# SCH_Lood_2024-08-15.net
KiCad netlist of a schematic drawn in EasyEDA
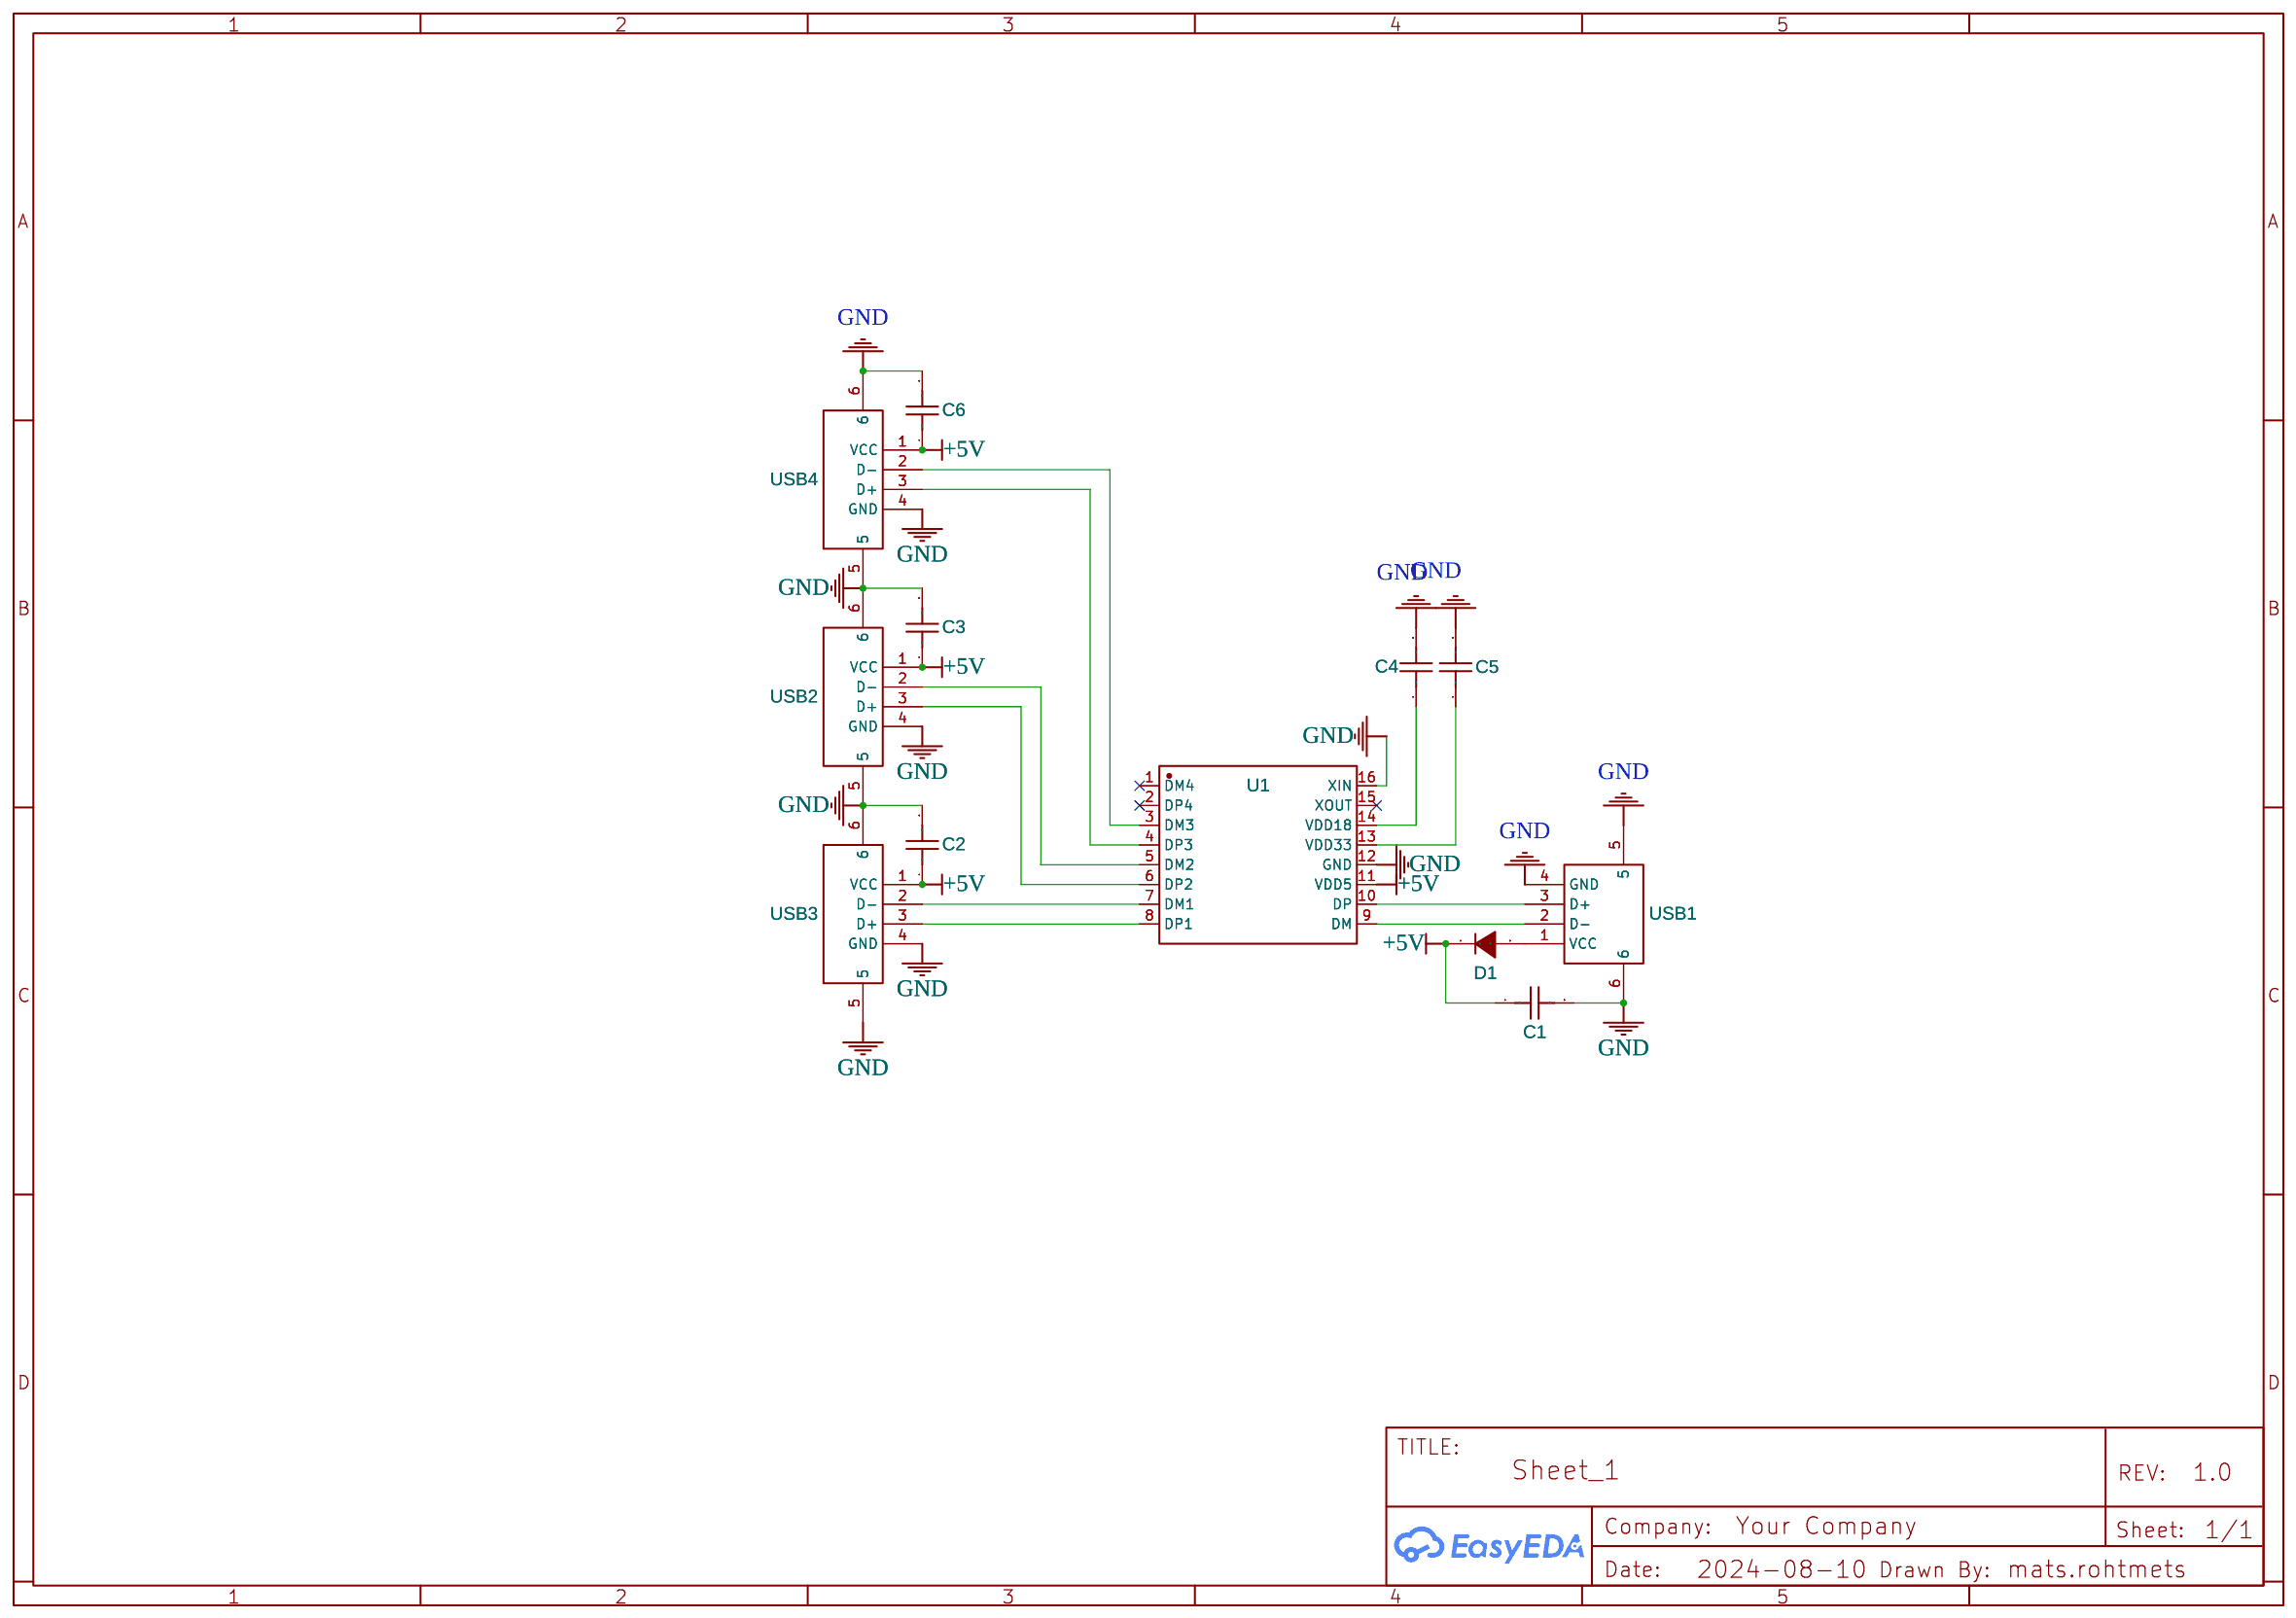
[diagram p0: schematic sheet]

(export (version "E")
  (design (tool "Eeschema 10.0.6"))
  (components
    (comp (ref "C1")
      (value "10uF")
      (fields
        (field (name "Manufacturer Part") "CL10A106KP8NNNC")
        (field (name "Manufacturer") "SAMSUNG(三星)")
      )
      (libsource (lib "") (part "CL10A106KP8NNNC_1"))
    )
    (comp (ref "C2")
      (value "10uF")
      (fields
        (field (name "Manufacturer Part") "CL10A106KP8NNNC")
        (field (name "Manufacturer") "SAMSUNG(三星)")
      )
      (libsource (lib "") (part "CL10A106KP8NNNC"))
    )
    (comp (ref "C3")
      (value "10uF")
      (fields
        (field (name "Manufacturer Part") "CL10A106KP8NNNC")
        (field (name "Manufacturer") "SAMSUNG(三星)")
      )
      (libsource (lib "") (part "CL10A106KP8NNNC"))
    )
    (comp (ref "C4")
      (value "10uF")
      (fields
        (field (name "Manufacturer Part") "CL10A106KP8NNNC")
        (field (name "Manufacturer") "SAMSUNG(三星)")
      )
      (libsource (lib "") (part "CL10A106KP8NNNC"))
    )
    (comp (ref "C5")
      (value "10uF")
      (fields
        (field (name "Manufacturer Part") "CL10A106KP8NNNC")
        (field (name "Manufacturer") "SAMSUNG(三星)")
      )
      (libsource (lib "") (part "CL10A106KP8NNNC"))
    )
    (comp (ref "C6")
      (value "10uF")
      (fields
        (field (name "Manufacturer Part") "CL10A106KP8NNNC")
        (field (name "Manufacturer") "SAMSUNG(三星)")
      )
      (libsource (lib "") (part "CL10A106KP8NNNC"))
    )
    (comp (ref "D1")
      (value "NSR0320MW2T1G")
      (fields (field (name "Manufacturer") "onsemi(安森美)"))
      (libsource (lib "") (part "NSR0320MW2T1G"))
    )
    (comp (ref "U1")
      (value "SL2.1A")
      (fields (field (name "Manufacturer") "CoreChips(和芯润德)"))
      (libsource (lib "") (part "SL2.1A"))
    )
    (comp (ref "USB1")
      (value "U-G-04DD-W-01")
      (fields (field (name "Manufacturer Part") "U-G-O4DD-W-1") (field (name "Manufacturer") "韩国韩荣"))
      (libsource (lib "") (part "U-G-04DD-W-01"))
    )
    (comp (ref "USB2")
      (value "USB-AF-90-14.4X13.6-H7.0-DIP")
      (fields (field (name "Manufacturer Part") "903-131A1011D10100") (field (name "Manufacturer") "精拓金"))
      (libsource (lib "") (part "USB-AF-90-14.4X13.6-H7.0-DIP"))
    )
    (comp (ref "USB3")
      (value "USB-AF-90-14.4X13.6-H7.0-DIP")
      (fields (field (name "Manufacturer Part") "903-131A1011D10100") (field (name "Manufacturer") "精拓金"))
      (libsource (lib "") (part "USB-AF-90-14.4X13.6-H7.0-DIP"))
    )
    (comp (ref "USB4")
      (value "USB-AF-90-14.4X13.6-H7.0-DIP")
      (fields (field (name "Manufacturer Part") "903-131A1011D10100") (field (name "Manufacturer") "精拓金"))
      (libsource (lib "") (part "USB-AF-90-14.4X13.6-H7.0-DIP"))
    )
  )
  (nets
    (net (code "1") (name "+5V") (class "Default")
      (node (ref "C1") (pin "1") (pinfunction "1_1") (pintype "unspecified"))
      (node (ref "C2") (pin "1") (pinfunction "1_1") (pintype "unspecified"))
      (node (ref "C3") (pin "1") (pinfunction "1_1") (pintype "unspecified"))
      (node (ref "C6") (pin "1") (pinfunction "1_1") (pintype "unspecified"))
      (node (ref "D1") (pin "1") (pinfunction "C_1") (pintype "unspecified"))
      (node (ref "U1") (pin "11") (pinfunction "VDD5_11") (pintype "unspecified"))
      (node (ref "USB2") (pin "1") (pinfunction "VCC_1") (pintype "unspecified"))
      (node (ref "USB3") (pin "1") (pinfunction "VCC_1") (pintype "unspecified"))
      (node (ref "USB4") (pin "1") (pinfunction "VCC_1") (pintype "unspecified"))
    )
    (net (code "2") (name "GND") (class "Default")
      (node (ref "C1") (pin "2") (pinfunction "2_2") (pintype "unspecified"))
      (node (ref "C2") (pin "2") (pinfunction "2_2") (pintype "unspecified"))
      (node (ref "C3") (pin "2") (pinfunction "2_2") (pintype "unspecified"))
      (node (ref "C4") (pin "2") (pinfunction "2_2") (pintype "unspecified"))
      (node (ref "C5") (pin "2") (pinfunction "2_2") (pintype "unspecified"))
      (node (ref "C6") (pin "2") (pinfunction "2_2") (pintype "unspecified"))
      (node (ref "U1") (pin "12") (pinfunction "GND_12") (pintype "unspecified"))
      (node (ref "U1") (pin "16") (pinfunction "XIN_16") (pintype "unspecified"))
      (node (ref "USB1") (pin "4") (pinfunction "GND_4") (pintype "unspecified"))
      (node (ref "USB1") (pin "5") (pinfunction "5_5") (pintype "unspecified"))
      (node (ref "USB1") (pin "6") (pinfunction "6_6") (pintype "unspecified"))
      (node (ref "USB2") (pin "4") (pinfunction "GND_4") (pintype "unspecified"))
      (node (ref "USB2") (pin "5") (pinfunction "5_5") (pintype "unspecified"))
      (node (ref "USB2") (pin "6") (pinfunction "6_6") (pintype "unspecified"))
      (node (ref "USB3") (pin "4") (pinfunction "GND_4") (pintype "unspecified"))
      (node (ref "USB3") (pin "5") (pinfunction "5_5") (pintype "unspecified"))
      (node (ref "USB3") (pin "6") (pinfunction "6_6") (pintype "unspecified"))
      (node (ref "USB4") (pin "4") (pinfunction "GND_4") (pintype "unspecified"))
      (node (ref "USB4") (pin "5") (pinfunction "5_5") (pintype "unspecified"))
      (node (ref "USB4") (pin "6") (pinfunction "6_6") (pintype "unspecified"))
    )
    (net (code "3") (name "Net-(D1-A)") (class "Default")
      (node (ref "D1") (pin "2") (pinfunction "A_2") (pintype "unspecified"))
      (node (ref "USB1") (pin "1") (pinfunction "VCC_1") (pintype "unspecified"))
    )
    (net (code "4") (name "Net-(U1-DM)") (class "Default")
      (node (ref "U1") (pin "9") (pinfunction "DM_9") (pintype "unspecified"))
      (node (ref "USB1") (pin "2") (pinfunction "D-_2") (pintype "unspecified"))
    )
    (net (code "5") (name "Net-(U1-DM1)") (class "Default")
      (node (ref "U1") (pin "7") (pinfunction "DM1_7") (pintype "unspecified"))
      (node (ref "USB3") (pin "2") (pinfunction "D-_2") (pintype "unspecified"))
    )
    (net (code "6") (name "Net-(U1-DM2)") (class "Default")
      (node (ref "U1") (pin "5") (pinfunction "DM2_5") (pintype "unspecified"))
      (node (ref "USB2") (pin "2") (pinfunction "D-_2") (pintype "unspecified"))
    )
    (net (code "7") (name "Net-(U1-DM3)") (class "Default")
      (node (ref "U1") (pin "3") (pinfunction "DM3_3") (pintype "unspecified"))
      (node (ref "USB4") (pin "2") (pinfunction "D-_2") (pintype "unspecified"))
    )
    (net (code "8") (name "Net-(U1-DP)") (class "Default")
      (node (ref "U1") (pin "10") (pinfunction "DP_10") (pintype "unspecified"))
      (node (ref "USB1") (pin "3") (pinfunction "D+_3") (pintype "unspecified"))
    )
    (net (code "9") (name "Net-(U1-DP1)") (class "Default")
      (node (ref "U1") (pin "8") (pinfunction "DP1_8") (pintype "unspecified"))
      (node (ref "USB3") (pin "3") (pinfunction "D+_3") (pintype "unspecified"))
    )
    (net (code "10") (name "Net-(U1-DP2)") (class "Default")
      (node (ref "U1") (pin "6") (pinfunction "DP2_6") (pintype "unspecified"))
      (node (ref "USB2") (pin "3") (pinfunction "D+_3") (pintype "unspecified"))
    )
    (net (code "11") (name "Net-(U1-DP3)") (class "Default")
      (node (ref "U1") (pin "4") (pinfunction "DP3_4") (pintype "unspecified"))
      (node (ref "USB4") (pin "3") (pinfunction "D+_3") (pintype "unspecified"))
    )
    (net (code "12") (name "Net-(U1-VDD18)") (class "Default")
      (node (ref "C4") (pin "1") (pinfunction "1_1") (pintype "unspecified"))
      (node (ref "U1") (pin "14") (pinfunction "VDD18_14") (pintype "unspecified"))
    )
    (net (code "13") (name "Net-(U1-VDD33)") (class "Default")
      (node (ref "C5") (pin "1") (pinfunction "1_1") (pintype "unspecified"))
      (node (ref "U1") (pin "13") (pinfunction "VDD33_13") (pintype "unspecified"))
    )
    (net (code "14") (name "unconnected-(U1-DM4-Pad1)") (class "Default")
      (node (ref "U1") (pin "1") (pinfunction "DM4_1") (pintype "unspecified+no_connect"))
    )
    (net (code "15") (name "unconnected-(U1-DP4-Pad2)") (class "Default")
      (node (ref "U1") (pin "2") (pinfunction "DP4_2") (pintype "unspecified+no_connect"))
    )
    (net (code "16") (name "unconnected-(U1-XOUT-Pad15)") (class "Default")
      (node (ref "U1") (pin "15") (pinfunction "XOUT_15") (pintype "unspecified+no_connect"))
    )
  )
)
